# brainwave.net
KiCad netlist of a schematic drawn in EAGLE
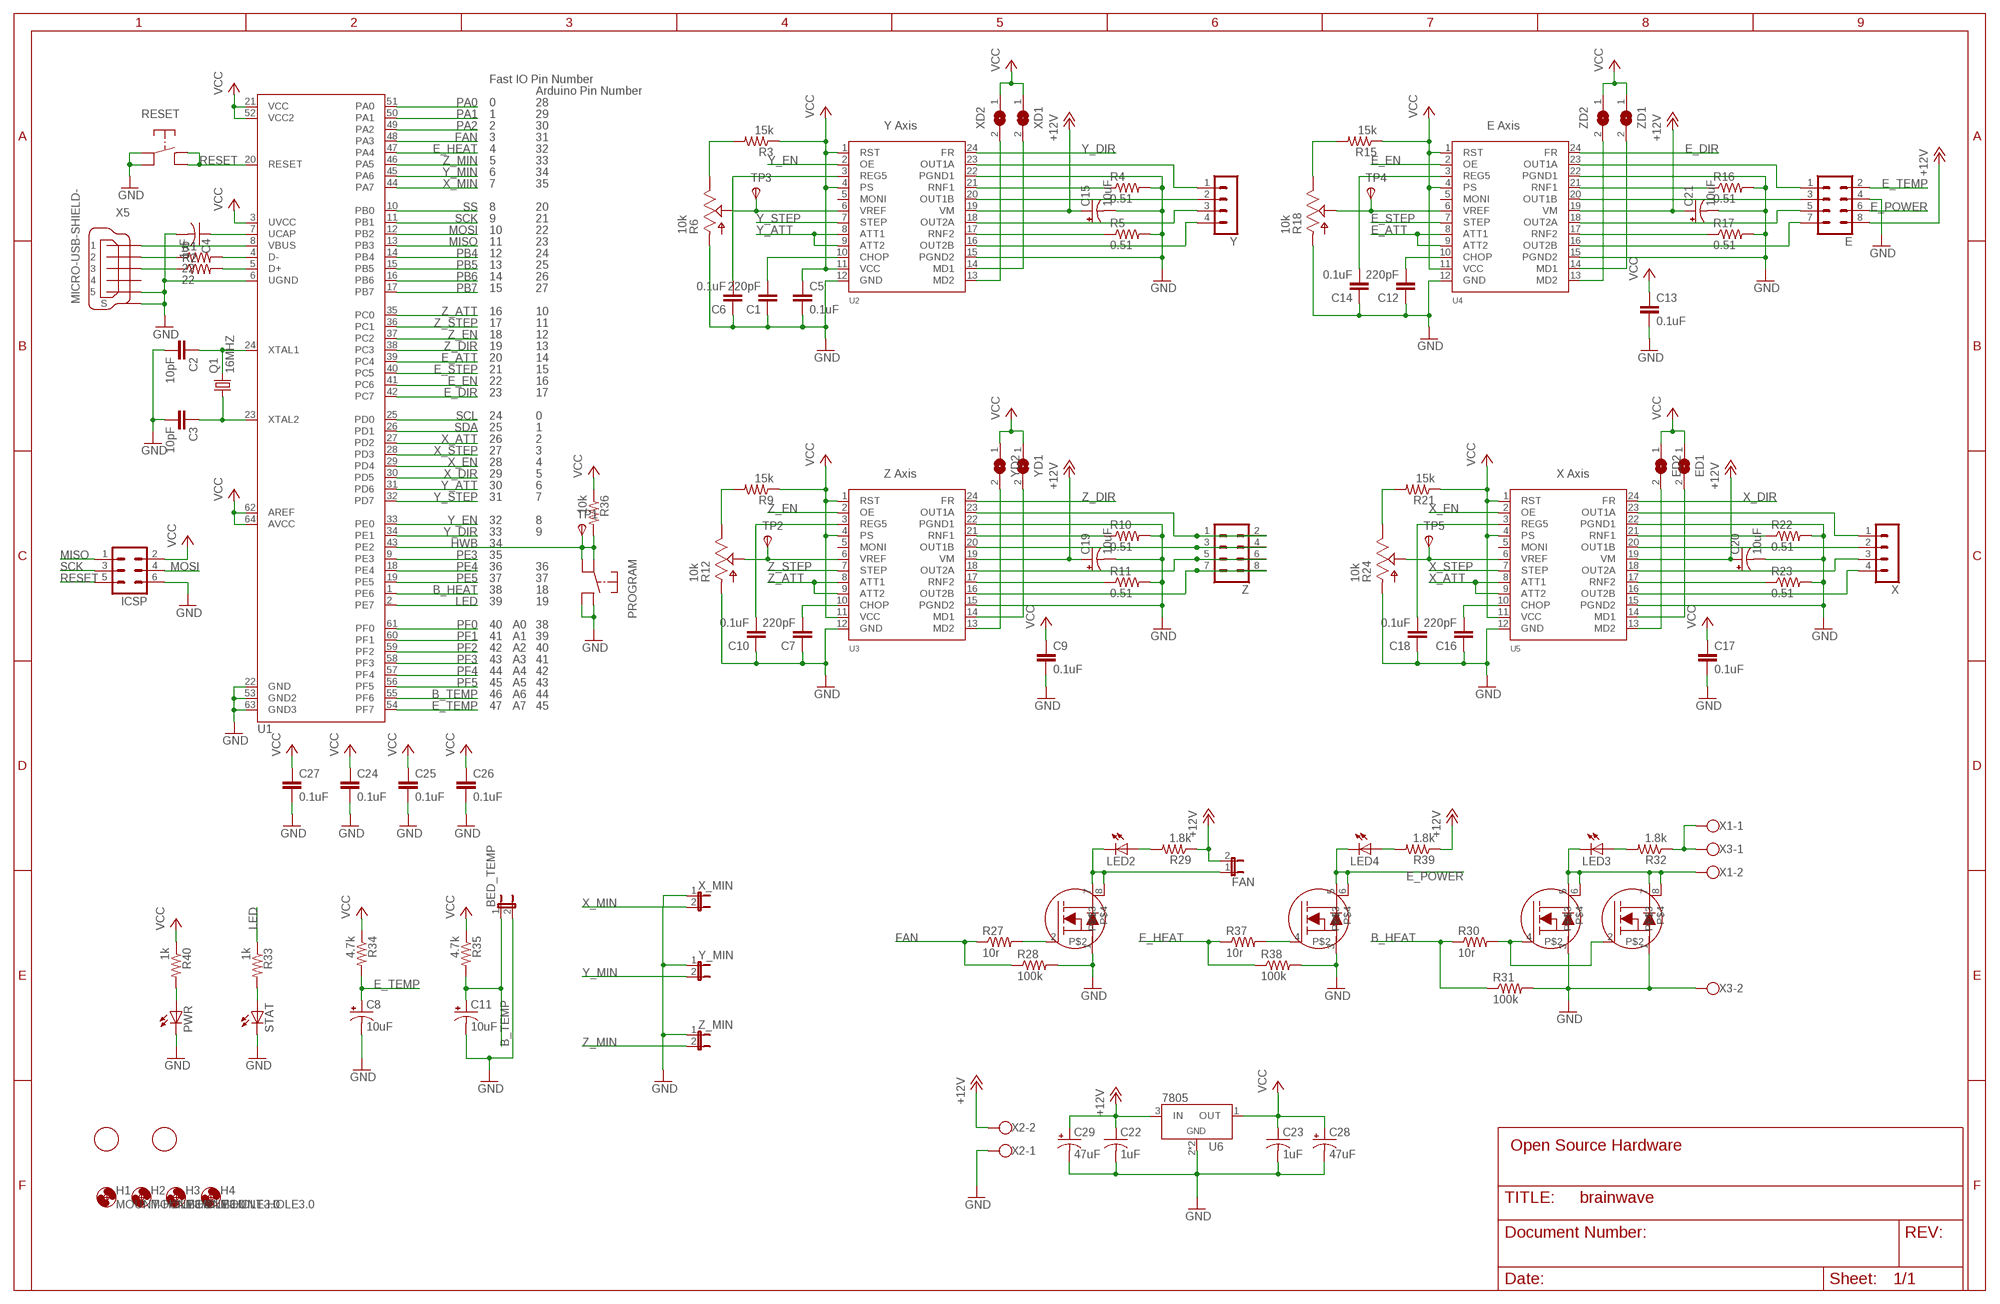
[diagram p0: schematic, sheet 1]

(export (version "E")
  (design (tool "Eeschema 10.0.6"))
  (components
    (comp (ref "BED_TEMP")
      (value "JP1E")
      (footprint "eagle-import:JP1")
      (libsource (lib "eagle-import") (part "JP1E"))
    )
    (comp (ref "C1")
      (value "220pF")
      (footprint "eagle-import:C0603")
      (libsource (lib "eagle-import") (part "C-EUC0603"))
    )
    (comp (ref "C2")
      (value "10pF")
      (footprint "eagle-import:C0603")
      (libsource (lib "eagle-import") (part "C-EUC0603"))
    )
    (comp (ref "C3")
      (value "10pF")
      (footprint "eagle-import:C0603")
      (libsource (lib "eagle-import") (part "C-EUC0603"))
    )
    (comp (ref "C4")
      (value "1uF")
      (footprint "eagle-import:C0603")
      (libsource (lib "eagle-import") (part "C-USC0603"))
    )
    (comp (ref "C5")
      (value "0.1uF")
      (footprint "eagle-import:C0603")
      (libsource (lib "eagle-import") (part "C-EUC0603"))
    )
    (comp (ref "C6")
      (value "0.1uF")
      (footprint "eagle-import:C0603")
      (libsource (lib "eagle-import") (part "C-EUC0603"))
    )
    (comp (ref "C7")
      (value "220pF")
      (footprint "eagle-import:C0603")
      (libsource (lib "eagle-import") (part "C-EUC0603"))
    )
    (comp (ref "C8")
      (value "10uF")
      (footprint "eagle-import:153CLV-0505")
      (libsource (lib "eagle-import") (part "CPOL-US153CLV-0505"))
    )
    (comp (ref "C9")
      (value "0.1uF")
      (footprint "eagle-import:C0603")
      (libsource (lib "eagle-import") (part "C-EUC0603"))
    )
    (comp (ref "C10")
      (value "0.1uF")
      (footprint "eagle-import:C0603")
      (libsource (lib "eagle-import") (part "C-EUC0603"))
    )
    (comp (ref "C11")
      (value "10uF")
      (footprint "eagle-import:153CLV-0505")
      (libsource (lib "eagle-import") (part "CPOL-US153CLV-0505"))
    )
    (comp (ref "C12")
      (value "220pF")
      (footprint "eagle-import:C0603")
      (libsource (lib "eagle-import") (part "C-EUC0603"))
    )
    (comp (ref "C13")
      (value "0.1uF")
      (footprint "eagle-import:C0603")
      (libsource (lib "eagle-import") (part "C-EUC0603"))
    )
    (comp (ref "C14")
      (value "0.1uF")
      (footprint "eagle-import:C0603")
      (libsource (lib "eagle-import") (part "C-EUC0603"))
    )
    (comp (ref "C15")
      (value "10uF")
      (footprint "eagle-import:153CLV-0505")
      (libsource (lib "eagle-import") (part "CPOL-US153CLV-0505"))
    )
    (comp (ref "C16")
      (value "220pF")
      (footprint "eagle-import:C0603")
      (libsource (lib "eagle-import") (part "C-EUC0603"))
    )
    (comp (ref "C17")
      (value "0.1uF")
      (footprint "eagle-import:C0603")
      (libsource (lib "eagle-import") (part "C-EUC0603"))
    )
    (comp (ref "C18")
      (value "0.1uF")
      (footprint "eagle-import:C0603")
      (libsource (lib "eagle-import") (part "C-EUC0603"))
    )
    (comp (ref "C19")
      (value "10uF")
      (footprint "eagle-import:153CLV-0505")
      (libsource (lib "eagle-import") (part "CPOL-US153CLV-0505"))
    )
    (comp (ref "C20")
      (value "10uF")
      (footprint "eagle-import:153CLV-0505")
      (libsource (lib "eagle-import") (part "CPOL-US153CLV-0505"))
    )
    (comp (ref "C21")
      (value "10uF")
      (footprint "eagle-import:153CLV-0505")
      (libsource (lib "eagle-import") (part "CPOL-US153CLV-0505"))
    )
    (comp (ref "C22")
      (value "1uF")
      (footprint "eagle-import:C0603")
      (libsource (lib "eagle-import") (part "C-USC0603"))
    )
    (comp (ref "C23")
      (value "1uF")
      (footprint "eagle-import:C0603")
      (libsource (lib "eagle-import") (part "C-USC0603"))
    )
    (comp (ref "C24")
      (value "0.1uF")
      (footprint "eagle-import:C0603")
      (libsource (lib "eagle-import") (part "C-EUC0603"))
    )
    (comp (ref "C25")
      (value "0.1uF")
      (footprint "eagle-import:C0603")
      (libsource (lib "eagle-import") (part "C-EUC0603"))
    )
    (comp (ref "C26")
      (value "0.1uF")
      (footprint "eagle-import:C0603")
      (libsource (lib "eagle-import") (part "C-EUC0603"))
    )
    (comp (ref "C27")
      (value "0.1uF")
      (footprint "eagle-import:C0603")
      (libsource (lib "eagle-import") (part "C-EUC0603"))
    )
    (comp (ref "C28")
      (value "47uF")
      (footprint "eagle-import:153CLV-0605")
      (libsource (lib "eagle-import") (part "CPOL-US153CLV-0605"))
    )
    (comp (ref "C29")
      (value "47uF")
      (footprint "eagle-import:153CLV-0605")
      (libsource (lib "eagle-import") (part "CPOL-US153CLV-0605"))
    )
    (comp (ref "E")
      (value "MA04-2")
      (footprint "eagle-import:MA04-2")
      (libsource (lib "eagle-import") (part "MA04-2"))
    )
    (comp (ref "ED1") (value "SJ") (footprint "eagle-import:SJ") (libsource (lib "eagle-import") (part "SJ")))
    (comp (ref "ED2") (value "SJ") (footprint "eagle-import:SJ") (libsource (lib "eagle-import") (part "SJ")))
    (comp (ref "FAN")
      (value "JP1E")
      (footprint "eagle-import:JP1")
      (libsource (lib "eagle-import") (part "JP1E"))
    )
    (comp (ref "H1")
      (value "MOUNT-HOLE3.0")
      (footprint "eagle-import:3,0")
      (libsource (lib "eagle-import") (part "MOUNT-HOLE3.0"))
    )
    (comp (ref "H2")
      (value "MOUNT-HOLE3.0")
      (footprint "eagle-import:3,0")
      (libsource (lib "eagle-import") (part "MOUNT-HOLE3.0"))
    )
    (comp (ref "H3")
      (value "MOUNT-HOLE3.0")
      (footprint "eagle-import:3,0")
      (libsource (lib "eagle-import") (part "MOUNT-HOLE3.0"))
    )
    (comp (ref "H4")
      (value "MOUNT-HOLE3.0")
      (footprint "eagle-import:3,0")
      (libsource (lib "eagle-import") (part "MOUNT-HOLE3.0"))
    )
    (comp (ref "ICSP")
      (value "MA03-2")
      (footprint "eagle-import:MA03-2")
      (libsource (lib "eagle-import") (part "MA03-2"))
    )
    (comp (ref "LED2")
      (value "LEDCHIPLED_0805")
      (footprint "eagle-import:CHIPLED_0805")
      (libsource (lib "eagle-import") (part "LEDCHIPLED_0805"))
    )
    (comp (ref "LED3")
      (value "LEDCHIPLED_0805")
      (footprint "eagle-import:CHIPLED_0805")
      (libsource (lib "eagle-import") (part "LEDCHIPLED_0805"))
    )
    (comp (ref "LED4")
      (value "LEDCHIPLED_0805")
      (footprint "eagle-import:CHIPLED_0805")
      (libsource (lib "eagle-import") (part "LEDCHIPLED_0805"))
    )
    (comp (ref "PROGRAM")
      (value "PTS645SMT")
      (footprint "eagle-import:PTS645-SMTR")
      (libsource (lib "eagle-import") (part "PTS645SMT"))
    )
    (comp (ref "PWR")
      (value "LEDCHIPLED_0805")
      (footprint "eagle-import:CHIPLED_0805")
      (libsource (lib "eagle-import") (part "LEDCHIPLED_0805"))
    )
    (comp (ref "Q1")
      (value "16MHZ")
      (footprint "eagle-import:CSM-3X")
      (libsource (lib "eagle-import") (part "CRYSTALCSM-3X"))
    )
    (comp (ref "R1")
      (value "22")
      (footprint "eagle-import:R0603")
      (libsource (lib "eagle-import") (part "R-US_R0603"))
    )
    (comp (ref "R2")
      (value "22")
      (footprint "eagle-import:R0603")
      (libsource (lib "eagle-import") (part "R-US_R0603"))
    )
    (comp (ref "R3")
      (value "15k")
      (footprint "eagle-import:R0603")
      (libsource (lib "eagle-import") (part "R-US_R0603"))
    )
    (comp (ref "R4")
      (value "0.51")
      (footprint "eagle-import:R2512")
      (libsource (lib "eagle-import") (part "R-US_R2512"))
    )
    (comp (ref "R5")
      (value "0.51")
      (footprint "eagle-import:R2512")
      (libsource (lib "eagle-import") (part "R-US_R2512"))
    )
    (comp (ref "R6")
      (value "10k")
      (footprint "eagle-import:PVZ3A")
      (libsource (lib "eagle-import") (part "PVZ3A"))
    )
    (comp (ref "R9")
      (value "15k")
      (footprint "eagle-import:R0603")
      (libsource (lib "eagle-import") (part "R-US_R0603"))
    )
    (comp (ref "R10")
      (value "0.51")
      (footprint "eagle-import:R2512")
      (libsource (lib "eagle-import") (part "R-US_R2512"))
    )
    (comp (ref "R11")
      (value "0.51")
      (footprint "eagle-import:R2512")
      (libsource (lib "eagle-import") (part "R-US_R2512"))
    )
    (comp (ref "R12")
      (value "10k")
      (footprint "eagle-import:PVZ3A")
      (libsource (lib "eagle-import") (part "PVZ3A"))
    )
    (comp (ref "R15")
      (value "15k")
      (footprint "eagle-import:R0603")
      (libsource (lib "eagle-import") (part "R-US_R0603"))
    )
    (comp (ref "R16")
      (value "0.51")
      (footprint "eagle-import:R2512")
      (libsource (lib "eagle-import") (part "R-US_R2512"))
    )
    (comp (ref "R17")
      (value "0.51")
      (footprint "eagle-import:R2512")
      (libsource (lib "eagle-import") (part "R-US_R2512"))
    )
    (comp (ref "R18")
      (value "10k")
      (footprint "eagle-import:PVZ3A")
      (libsource (lib "eagle-import") (part "PVZ3A"))
    )
    (comp (ref "R21")
      (value "15k")
      (footprint "eagle-import:R0603")
      (libsource (lib "eagle-import") (part "R-US_R0603"))
    )
    (comp (ref "R22")
      (value "0.51")
      (footprint "eagle-import:R2512")
      (libsource (lib "eagle-import") (part "R-US_R2512"))
    )
    (comp (ref "R23")
      (value "0.51")
      (footprint "eagle-import:R2512")
      (libsource (lib "eagle-import") (part "R-US_R2512"))
    )
    (comp (ref "R24")
      (value "10k")
      (footprint "eagle-import:PVZ3A")
      (libsource (lib "eagle-import") (part "PVZ3A"))
    )
    (comp (ref "R27")
      (value "10r")
      (footprint "eagle-import:R0603")
      (libsource (lib "eagle-import") (part "R-US_R0603"))
    )
    (comp (ref "R28")
      (value "100k")
      (footprint "eagle-import:R0603")
      (libsource (lib "eagle-import") (part "R-US_R0603"))
    )
    (comp (ref "R29")
      (value "1.8k")
      (footprint "eagle-import:R0603")
      (libsource (lib "eagle-import") (part "R-US_R0603"))
    )
    (comp (ref "R30")
      (value "10r")
      (footprint "eagle-import:R0603")
      (libsource (lib "eagle-import") (part "R-US_R0603"))
    )
    (comp (ref "R31")
      (value "100k")
      (footprint "eagle-import:R0603")
      (libsource (lib "eagle-import") (part "R-US_R0603"))
    )
    (comp (ref "R32")
      (value "1.8k")
      (footprint "eagle-import:R0603")
      (libsource (lib "eagle-import") (part "R-US_R0603"))
    )
    (comp (ref "R33")
      (value "1k")
      (footprint "eagle-import:R0603")
      (libsource (lib "eagle-import") (part "R-US_R0603"))
    )
    (comp (ref "R34")
      (value "4.7k")
      (footprint "eagle-import:R0603")
      (libsource (lib "eagle-import") (part "R-US_R0603"))
    )
    (comp (ref "R35")
      (value "4.7k")
      (footprint "eagle-import:R0603")
      (libsource (lib "eagle-import") (part "R-US_R0603"))
    )
    (comp (ref "R36")
      (value "10k")
      (footprint "eagle-import:R0603")
      (libsource (lib "eagle-import") (part "R-US_R0603"))
    )
    (comp (ref "R37")
      (value "10r")
      (footprint "eagle-import:R0603")
      (libsource (lib "eagle-import") (part "R-US_R0603"))
    )
    (comp (ref "R38")
      (value "100k")
      (footprint "eagle-import:R0603")
      (libsource (lib "eagle-import") (part "R-US_R0603"))
    )
    (comp (ref "R39")
      (value "1.8k")
      (footprint "eagle-import:R0603")
      (libsource (lib "eagle-import") (part "R-US_R0603"))
    )
    (comp (ref "R40")
      (value "1k")
      (footprint "eagle-import:R0603")
      (libsource (lib "eagle-import") (part "R-US_R0603"))
    )
    (comp (ref "RESET")
      (value "PTS645SMT")
      (footprint "eagle-import:PTS645-SMTR")
      (libsource (lib "eagle-import") (part "PTS645SMT"))
    )
    (comp (ref "STAT")
      (value "LEDCHIPLED_0805")
      (footprint "eagle-import:CHIPLED_0805")
      (libsource (lib "eagle-import") (part "LEDCHIPLED_0805"))
    )
    (comp (ref "TP1")
      (value "TPSTP08R")
      (footprint "eagle-import:TP08R")
      (libsource (lib "eagle-import") (part "TPSTP08R"))
    )
    (comp (ref "TP2")
      (value "TPSTP08R")
      (footprint "eagle-import:TP08R")
      (libsource (lib "eagle-import") (part "TPSTP08R"))
    )
    (comp (ref "TP3")
      (value "TPSTP08R")
      (footprint "eagle-import:TP08R")
      (libsource (lib "eagle-import") (part "TPSTP08R"))
    )
    (comp (ref "TP4")
      (value "TPSTP08R")
      (footprint "eagle-import:TP08R")
      (libsource (lib "eagle-import") (part "TPSTP08R"))
    )
    (comp (ref "TP5")
      (value "TPSTP08R")
      (footprint "eagle-import:TP08R")
      (libsource (lib "eagle-import") (part "TPSTP08R"))
    )
    (comp (ref "U$1")
      (value "FIDUCIAL")
      (footprint "eagle-import:FIDUCIAL_1MM")
      (libsource (lib "eagle-import") (part "FIDUCIAL"))
    )
    (comp (ref "U$2")
      (value "FIDUCIAL")
      (footprint "eagle-import:FIDUCIAL_1MM")
      (libsource (lib "eagle-import") (part "FIDUCIAL"))
    )
    (comp (ref "U1")
      (value "AT90USB64/128")
      (footprint "eagle-import:TQFP64")
      (libsource (lib "eagle-import") (part "AT90USB64/128"))
    )
    (comp (ref "U2")
      (value "LV8713T")
      (footprint "eagle-import:TSSOP24")
      (libsource (lib "eagle-import") (part "LV8713T"))
    )
    (comp (ref "U3")
      (value "LV8713T")
      (footprint "eagle-import:TSSOP24")
      (libsource (lib "eagle-import") (part "LV8713T"))
    )
    (comp (ref "U4")
      (value "LV8713T")
      (footprint "eagle-import:TSSOP24")
      (libsource (lib "eagle-import") (part "LV8713T"))
    )
    (comp (ref "U5")
      (value "LV8713T")
      (footprint "eagle-import:TSSOP24")
      (libsource (lib "eagle-import") (part "LV8713T"))
    )
    (comp (ref "U6")
      (value "7805")
      (footprint "eagle-import:SOT89")
      (libsource (lib "eagle-import") (part "78"))
    )
    (comp (ref "U7")
      (value "IRF8313PBF")
      (footprint "eagle-import:SO8")
      (libsource (lib "eagle-import") (part "IRF8313PBF"))
    )
    (comp (ref "U8")
      (value "IRF8313PBF")
      (footprint "eagle-import:SO8")
      (libsource (lib "eagle-import") (part "IRF8313PBF"))
    )
    (comp (ref "X")
      (value "MA04-1")
      (footprint "eagle-import:MA04-1")
      (libsource (lib "eagle-import") (part "MA04-1"))
    )
    (comp (ref "X1")
      (value "W237-102")
      (footprint "eagle-import:W237-102")
      (fields
        (field (name "MPN") "237-102")
        (field (name "MPN_1") "237-102")
        (field (name "OC_FARNELL") "unknown")
        (field (name "OC_NEWARK") "70K9898")
      )
      (libsource (lib "eagle-import") (part "W237-102"))
    )
    (comp (ref "X2")
      (value "W237-102")
      (footprint "eagle-import:W237-102")
      (fields (field (name "MPN") "237-102"))
      (libsource (lib "eagle-import") (part "W237-102"))
    )
    (comp (ref "X3")
      (value "W237-102")
      (footprint "eagle-import:W237-102")
      (fields
        (field (name "MPN") "237-102")
        (field (name "MPN_1") "237-102")
        (field (name "OC_FARNELL") "unknown")
        (field (name "OC_NEWARK") "70K9898")
      )
      (libsource (lib "eagle-import") (part "W237-102"))
    )
    (comp (ref "X5")
      (value "MICRO-USB-SHIELD-")
      (footprint "eagle-import:10118192-0001LF")
      (libsource (lib "eagle-import") (part "MICRO-USB-SHIELD-"))
    )
    (comp (ref "XD1") (value "SJ") (footprint "eagle-import:SJ") (libsource (lib "eagle-import") (part "SJ")))
    (comp (ref "XD2") (value "SJ") (footprint "eagle-import:SJ") (libsource (lib "eagle-import") (part "SJ")))
    (comp (ref "X_MIN")
      (value "JP1E")
      (footprint "eagle-import:JP1")
      (libsource (lib "eagle-import") (part "JP1E"))
    )
    (comp (ref "Y")
      (value "MA04-1")
      (footprint "eagle-import:MA04-1")
      (libsource (lib "eagle-import") (part "MA04-1"))
    )
    (comp (ref "YD1") (value "SJ") (footprint "eagle-import:SJ") (libsource (lib "eagle-import") (part "SJ")))
    (comp (ref "YD2") (value "SJ") (footprint "eagle-import:SJ") (libsource (lib "eagle-import") (part "SJ")))
    (comp (ref "Y_MIN")
      (value "JP1E")
      (footprint "eagle-import:JP1")
      (libsource (lib "eagle-import") (part "JP1E"))
    )
    (comp (ref "Z")
      (value "MA04-2")
      (footprint "eagle-import:MA04-2")
      (libsource (lib "eagle-import") (part "MA04-2"))
    )
    (comp (ref "ZD1") (value "SJ") (footprint "eagle-import:SJ") (libsource (lib "eagle-import") (part "SJ")))
    (comp (ref "ZD2") (value "SJ") (footprint "eagle-import:SJ") (libsource (lib "eagle-import") (part "SJ")))
    (comp (ref "Z_MIN")
      (value "JP1E")
      (footprint "eagle-import:JP1")
      (libsource (lib "eagle-import") (part "JP1E"))
    )
  )
  (nets
    (net (code "1") (name "+12V") (class "Default")
      (node (ref "C15") (pin "+") (pinfunction "+_+") (pintype "passive"))
      (node (ref "C19") (pin "+") (pinfunction "+_+") (pintype "passive"))
      (node (ref "C20") (pin "+") (pinfunction "+_+") (pintype "passive"))
      (node (ref "C21") (pin "+") (pinfunction "+_+") (pintype "passive"))
      (node (ref "C22") (pin "1") (pinfunction "1_1") (pintype "passive"))
      (node (ref "C29") (pin "+") (pinfunction "+_+") (pintype "passive"))
      (node (ref "E") (pin "8") (pinfunction "8_8") (pintype "passive"))
      (node (ref "FAN") (pin "2") (pinfunction "2_2") (pintype "passive"))
      (node (ref "R29") (pin "1") (pinfunction "1_1") (pintype "passive"))
      (node (ref "R39") (pin "1") (pinfunction "1_1") (pintype "passive"))
      (node (ref "U2") (pin "19") (pinfunction "VM_19") (pintype "bidirectional"))
      (node (ref "U3") (pin "19") (pinfunction "VM_19") (pintype "bidirectional"))
      (node (ref "U4") (pin "19") (pinfunction "VM_19") (pintype "bidirectional"))
      (node (ref "U5") (pin "19") (pinfunction "VM_19") (pintype "bidirectional"))
      (node (ref "U6") (pin "3") (pinfunction "IN_3") (pintype "input"))
      (node (ref "X2") (pin "2") (pinfunction "KL_2") (pintype "passive"))
    )
    (net (code "2") (name "/B_HEAT") (class "Default")
      (node (ref "R30") (pin "1") (pinfunction "1_1") (pintype "passive"))
      (node (ref "R31") (pin "1") (pinfunction "1_1") (pintype "passive"))
      (node (ref "U1") (pin "1") (pinfunction "PE6_1") (pintype "bidirectional"))
    )
    (net (code "3") (name "/B_TEMP") (class "Default")
      (node (ref "BED_TEMP") (pin "1") (pinfunction "1_1") (pintype "passive"))
      (node (ref "C11") (pin "+") (pinfunction "+_+") (pintype "passive"))
      (node (ref "R35") (pin "2") (pinfunction "2_2") (pintype "passive"))
      (node (ref "U1") (pin "55") (pinfunction "PF6_55") (pintype "bidirectional"))
    )
    (net (code "4") (name "/E_ATT") (class "Default")
      (node (ref "U1") (pin "39") (pinfunction "PC4_39") (pintype "bidirectional"))
      (node (ref "U4") (pin "8") (pinfunction "ATT1_8") (pintype "bidirectional"))
      (node (ref "U4") (pin "9") (pinfunction "ATT2_9") (pintype "bidirectional"))
    )
    (net (code "5") (name "/E_DIR") (class "Default")
      (node (ref "U1") (pin "42") (pinfunction "PC7_42") (pintype "bidirectional"))
      (node (ref "U4") (pin "24") (pinfunction "FR_24") (pintype "bidirectional"))
    )
    (net (code "6") (name "/E_EN") (class "Default")
      (node (ref "U1") (pin "41") (pinfunction "PC6_41") (pintype "bidirectional"))
      (node (ref "U4") (pin "2") (pinfunction "OE_2") (pintype "bidirectional"))
    )
    (net (code "7") (name "/E_HEAT") (class "Default")
      (node (ref "R37") (pin "1") (pinfunction "1_1") (pintype "passive"))
      (node (ref "R38") (pin "1") (pinfunction "1_1") (pintype "passive"))
      (node (ref "U1") (pin "47") (pinfunction "PA4_47") (pintype "bidirectional"))
    )
    (net (code "8") (name "/E_POWER") (class "Default")
      (node (ref "E") (pin "6") (pinfunction "6_6") (pintype "passive"))
      (node (ref "LED4") (pin "C") (pinfunction "C_C") (pintype "passive"))
      (node (ref "U7") (pin "5") (pinfunction "P$3_5") (pintype "bidirectional"))
      (node (ref "U7") (pin "6") (pinfunction "P$4_6") (pintype "bidirectional"))
    )
    (net (code "9") (name "/E_STEP") (class "Default")
      (node (ref "U1") (pin "40") (pinfunction "PC5_40") (pintype "bidirectional"))
      (node (ref "U4") (pin "7") (pinfunction "STEP_7") (pintype "bidirectional"))
    )
    (net (code "10") (name "/E_TEMP") (class "Default")
      (node (ref "C8") (pin "+") (pinfunction "+_+") (pintype "passive"))
      (node (ref "E") (pin "2") (pinfunction "2_2") (pintype "passive"))
      (node (ref "R34") (pin "2") (pinfunction "2_2") (pintype "passive"))
      (node (ref "U1") (pin "54") (pinfunction "PF7_54") (pintype "bidirectional"))
    )
    (net (code "11") (name "/FAN") (class "Default")
      (node (ref "R27") (pin "1") (pinfunction "1_1") (pintype "passive"))
      (node (ref "R28") (pin "1") (pinfunction "1_1") (pintype "passive"))
      (node (ref "U1") (pin "48") (pinfunction "PA3_48") (pintype "bidirectional"))
    )
    (net (code "12") (name "/HWB") (class "Default")
      (node (ref "PROGRAM") (pin "P$1") (pinfunction "P$1_P$1") (pintype "bidirectional"))
      (node (ref "PROGRAM") (pin "P$2") (pinfunction "P$2_P$2") (pintype "bidirectional"))
      (node (ref "R36") (pin "2") (pinfunction "2_2") (pintype "passive"))
      (node (ref "TP1") (pin "TP") (pinfunction "PP_TP") (pintype "input"))
      (node (ref "U1") (pin "43") (pinfunction "PE2_43") (pintype "bidirectional"))
    )
    (net (code "13") (name "/LED") (class "Default")
      (node (ref "R33") (pin "1") (pinfunction "1_1") (pintype "passive"))
      (node (ref "U1") (pin "2") (pinfunction "PE7_2") (pintype "bidirectional"))
    )
    (net (code "14") (name "/MISO") (class "Default")
      (node (ref "ICSP") (pin "1") (pinfunction "1_1") (pintype "passive"))
      (node (ref "U1") (pin "13") (pinfunction "PB3_13") (pintype "bidirectional"))
    )
    (net (code "15") (name "/MOSI") (class "Default")
      (node (ref "ICSP") (pin "4") (pinfunction "4_4") (pintype "passive"))
      (node (ref "U1") (pin "12") (pinfunction "PB2_12") (pintype "bidirectional"))
    )
    (net (code "16") (name "/PA0") (class "Default")
      (node (ref "U1") (pin "51") (pinfunction "PA0_51") (pintype "bidirectional"))
    )
    (net (code "17") (name "/PA1") (class "Default")
      (node (ref "U1") (pin "50") (pinfunction "PA1_50") (pintype "bidirectional"))
    )
    (net (code "18") (name "/PA2") (class "Default")
      (node (ref "U1") (pin "49") (pinfunction "PA2_49") (pintype "bidirectional"))
    )
    (net (code "19") (name "/PB4") (class "Default")
      (node (ref "U1") (pin "14") (pinfunction "PB4_14") (pintype "bidirectional"))
    )
    (net (code "20") (name "/PB5") (class "Default")
      (node (ref "U1") (pin "15") (pinfunction "PB5_15") (pintype "bidirectional"))
    )
    (net (code "21") (name "/PB6") (class "Default")
      (node (ref "U1") (pin "16") (pinfunction "PB6_16") (pintype "bidirectional"))
    )
    (net (code "22") (name "/PB7") (class "Default")
      (node (ref "U1") (pin "17") (pinfunction "PB7_17") (pintype "bidirectional"))
    )
    (net (code "23") (name "/PE3") (class "Default")
      (node (ref "U1") (pin "9") (pinfunction "PE3_9") (pintype "bidirectional"))
    )
    (net (code "24") (name "/PE4") (class "Default")
      (node (ref "U1") (pin "18") (pinfunction "PE4_18") (pintype "bidirectional"))
    )
    (net (code "25") (name "/PE5") (class "Default")
      (node (ref "U1") (pin "19") (pinfunction "PE5_19") (pintype "bidirectional"))
    )
    (net (code "26") (name "/PF0") (class "Default")
      (node (ref "U1") (pin "61") (pinfunction "PF0_61") (pintype "bidirectional"))
    )
    (net (code "27") (name "/PF1") (class "Default")
      (node (ref "U1") (pin "60") (pinfunction "PF1_60") (pintype "bidirectional"))
    )
    (net (code "28") (name "/PF2") (class "Default")
      (node (ref "U1") (pin "59") (pinfunction "PF2_59") (pintype "bidirectional"))
    )
    (net (code "29") (name "/PF3") (class "Default")
      (node (ref "U1") (pin "58") (pinfunction "PF3_58") (pintype "bidirectional"))
    )
    (net (code "30") (name "/PF4") (class "Default")
      (node (ref "U1") (pin "57") (pinfunction "PF4_57") (pintype "bidirectional"))
    )
    (net (code "31") (name "/PF5") (class "Default")
      (node (ref "U1") (pin "56") (pinfunction "PF5_56") (pintype "bidirectional"))
    )
    (net (code "32") (name "/RESET") (class "Default")
      (node (ref "ICSP") (pin "5") (pinfunction "5_5") (pintype "passive"))
      (node (ref "RESET") (pin "P$3") (pinfunction "P$3_P$3") (pintype "bidirectional"))
      (node (ref "RESET") (pin "P$4") (pinfunction "P$4_P$4") (pintype "bidirectional"))
      (node (ref "U1") (pin "20") (pinfunction "RESET_20") (pintype "bidirectional"))
    )
    (net (code "33") (name "/SCK") (class "Default")
      (node (ref "ICSP") (pin "3") (pinfunction "3_3") (pintype "passive"))
      (node (ref "U1") (pin "11") (pinfunction "PB1_11") (pintype "bidirectional"))
    )
    (net (code "34") (name "/SCL") (class "Default")
      (node (ref "U1") (pin "25") (pinfunction "PD0_25") (pintype "bidirectional"))
    )
    (net (code "35") (name "/SDA") (class "Default")
      (node (ref "U1") (pin "26") (pinfunction "PD1_26") (pintype "bidirectional"))
    )
    (net (code "36") (name "/SS") (class "Default")
      (node (ref "U1") (pin "10") (pinfunction "PB0_10") (pintype "bidirectional"))
    )
    (net (code "37") (name "/X_ATT") (class "Default")
      (node (ref "U1") (pin "27") (pinfunction "PD2_27") (pintype "bidirectional"))
      (node (ref "U5") (pin "8") (pinfunction "ATT1_8") (pintype "bidirectional"))
      (node (ref "U5") (pin "9") (pinfunction "ATT2_9") (pintype "bidirectional"))
    )
    (net (code "38") (name "/X_DIR") (class "Default")
      (node (ref "U1") (pin "30") (pinfunction "PD5_30") (pintype "bidirectional"))
      (node (ref "U5") (pin "24") (pinfunction "FR_24") (pintype "bidirectional"))
    )
    (net (code "39") (name "/X_EN") (class "Default")
      (node (ref "U1") (pin "29") (pinfunction "PD4_29") (pintype "bidirectional"))
      (node (ref "U5") (pin "2") (pinfunction "OE_2") (pintype "bidirectional"))
    )
    (net (code "40") (name "/X_MIN") (class "Default")
      (node (ref "U1") (pin "44") (pinfunction "PA7_44") (pintype "bidirectional"))
      (node (ref "X_MIN") (pin "2") (pinfunction "2_2") (pintype "passive"))
    )
    (net (code "41") (name "/X_STEP") (class "Default")
      (node (ref "U1") (pin "28") (pinfunction "PD3_28") (pintype "bidirectional"))
      (node (ref "U5") (pin "7") (pinfunction "STEP_7") (pintype "bidirectional"))
    )
    (net (code "42") (name "/Y_ATT") (class "Default")
      (node (ref "U1") (pin "31") (pinfunction "PD6_31") (pintype "bidirectional"))
      (node (ref "U2") (pin "8") (pinfunction "ATT1_8") (pintype "bidirectional"))
      (node (ref "U2") (pin "9") (pinfunction "ATT2_9") (pintype "bidirectional"))
    )
    (net (code "43") (name "/Y_DIR") (class "Default")
      (node (ref "U1") (pin "34") (pinfunction "PE1_34") (pintype "bidirectional"))
      (node (ref "U2") (pin "24") (pinfunction "FR_24") (pintype "bidirectional"))
    )
    (net (code "44") (name "/Y_EN") (class "Default")
      (node (ref "U1") (pin "33") (pinfunction "PE0_33") (pintype "bidirectional"))
      (node (ref "U2") (pin "2") (pinfunction "OE_2") (pintype "bidirectional"))
    )
    (net (code "45") (name "/Y_MIN") (class "Default")
      (node (ref "U1") (pin "45") (pinfunction "PA6_45") (pintype "bidirectional"))
      (node (ref "Y_MIN") (pin "2") (pinfunction "2_2") (pintype "passive"))
    )
    (net (code "46") (name "/Y_STEP") (class "Default")
      (node (ref "U1") (pin "32") (pinfunction "PD7_32") (pintype "bidirectional"))
      (node (ref "U2") (pin "7") (pinfunction "STEP_7") (pintype "bidirectional"))
    )
    (net (code "47") (name "/Z_ATT") (class "Default")
      (node (ref "U1") (pin "35") (pinfunction "PC0_35") (pintype "bidirectional"))
      (node (ref "U3") (pin "8") (pinfunction "ATT1_8") (pintype "bidirectional"))
      (node (ref "U3") (pin "9") (pinfunction "ATT2_9") (pintype "bidirectional"))
    )
    (net (code "48") (name "/Z_DIR") (class "Default")
      (node (ref "U1") (pin "38") (pinfunction "PC3_38") (pintype "bidirectional"))
      (node (ref "U3") (pin "24") (pinfunction "FR_24") (pintype "bidirectional"))
    )
    (net (code "49") (name "/Z_EN") (class "Default")
      (node (ref "U1") (pin "37") (pinfunction "PC2_37") (pintype "bidirectional"))
      (node (ref "U3") (pin "2") (pinfunction "OE_2") (pintype "bidirectional"))
    )
    (net (code "50") (name "/Z_MIN") (class "Default")
      (node (ref "U1") (pin "46") (pinfunction "PA5_46") (pintype "bidirectional"))
      (node (ref "Z_MIN") (pin "2") (pinfunction "2_2") (pintype "passive"))
    )
    (net (code "51") (name "/Z_STEP") (class "Default")
      (node (ref "U1") (pin "36") (pinfunction "PC1_36") (pintype "bidirectional"))
      (node (ref "U3") (pin "7") (pinfunction "STEP_7") (pintype "bidirectional"))
    )
    (net (code "52") (name "GND") (class "Default")
      (node (ref "BED_TEMP") (pin "2") (pinfunction "2_2") (pintype "passive"))
      (node (ref "C1") (pin "1") (pinfunction "1_1") (pintype "passive"))
      (node (ref "C10") (pin "1") (pinfunction "1_1") (pintype "passive"))
      (node (ref "C11") (pin "-") (pinfunction "-_-") (pintype "passive"))
      (node (ref "C12") (pin "1") (pinfunction "1_1") (pintype "passive"))
      (node (ref "C13") (pin "2") (pinfunction "2_2") (pintype "passive"))
      (node (ref "C14") (pin "1") (pinfunction "1_1") (pintype "passive"))
      (node (ref "C15") (pin "-") (pinfunction "-_-") (pintype "passive"))
      (node (ref "C16") (pin "1") (pinfunction "1_1") (pintype "passive"))
      (node (ref "C17") (pin "2") (pinfunction "2_2") (pintype "passive"))
      (node (ref "C18") (pin "1") (pinfunction "1_1") (pintype "passive"))
      (node (ref "C19") (pin "-") (pinfunction "-_-") (pintype "passive"))
      (node (ref "C2") (pin "2") (pinfunction "2_2") (pintype "passive"))
      (node (ref "C20") (pin "-") (pinfunction "-_-") (pintype "passive"))
      (node (ref "C21") (pin "-") (pinfunction "-_-") (pintype "passive"))
      (node (ref "C22") (pin "2") (pinfunction "2_2") (pintype "passive"))
      (node (ref "C23") (pin "2") (pinfunction "2_2") (pintype "passive"))
      (node (ref "C24") (pin "2") (pinfunction "2_2") (pintype "passive"))
      (node (ref "C25") (pin "2") (pinfunction "2_2") (pintype "passive"))
      (node (ref "C26") (pin "2") (pinfunction "2_2") (pintype "passive"))
      (node (ref "C27") (pin "2") (pinfunction "2_2") (pintype "passive"))
      (node (ref "C28") (pin "-") (pinfunction "-_-") (pintype "passive"))
      (node (ref "C29") (pin "-") (pinfunction "-_-") (pintype "passive"))
      (node (ref "C3") (pin "2") (pinfunction "2_2") (pintype "passive"))
      (node (ref "C4") (pin "2") (pinfunction "2_2") (pintype "passive"))
      (node (ref "C5") (pin "2") (pinfunction "2_2") (pintype "passive"))
      (node (ref "C6") (pin "1") (pinfunction "1_1") (pintype "passive"))
      (node (ref "C7") (pin "1") (pinfunction "1_1") (pintype "passive"))
      (node (ref "C8") (pin "-") (pinfunction "-_-") (pintype "passive"))
      (node (ref "C9") (pin "2") (pinfunction "2_2") (pintype "passive"))
      (node (ref "E") (pin "4") (pinfunction "4_4") (pintype "passive"))
      (node (ref "ICSP") (pin "6") (pinfunction "6_6") (pintype "passive"))
      (node (ref "PROGRAM") (pin "P$3") (pinfunction "P$3_P$3") (pintype "bidirectional"))
      (node (ref "PROGRAM") (pin "P$4") (pinfunction "P$4_P$4") (pintype "bidirectional"))
      (node (ref "PWR") (pin "C") (pinfunction "C_C") (pintype "passive"))
      (node (ref "R10") (pin "2") (pinfunction "2_2") (pintype "passive"))
      (node (ref "R11") (pin "2") (pinfunction "2_2") (pintype "passive"))
      (node (ref "R12") (pin "P$1") (pinfunction "P$1_P$1") (pintype "bidirectional"))
      (node (ref "R16") (pin "2") (pinfunction "2_2") (pintype "passive"))
      (node (ref "R17") (pin "2") (pinfunction "2_2") (pintype "passive"))
      (node (ref "R18") (pin "P$1") (pinfunction "P$1_P$1") (pintype "bidirectional"))
      (node (ref "R22") (pin "2") (pinfunction "2_2") (pintype "passive"))
      (node (ref "R23") (pin "2") (pinfunction "2_2") (pintype "passive"))
      (node (ref "R24") (pin "P$1") (pinfunction "P$1_P$1") (pintype "bidirectional"))
      (node (ref "R28") (pin "2") (pinfunction "2_2") (pintype "passive"))
      (node (ref "R31") (pin "2") (pinfunction "2_2") (pintype "passive"))
      (node (ref "R38") (pin "2") (pinfunction "2_2") (pintype "passive"))
      (node (ref "R4") (pin "2") (pinfunction "2_2") (pintype "passive"))
      (node (ref "R5") (pin "2") (pinfunction "2_2") (pintype "passive"))
      (node (ref "R6") (pin "P$1") (pinfunction "P$1_P$1") (pintype "bidirectional"))
      (node (ref "RESET") (pin "P$1") (pinfunction "P$1_P$1") (pintype "bidirectional"))
      (node (ref "RESET") (pin "P$2") (pinfunction "P$2_P$2") (pintype "bidirectional"))
      (node (ref "STAT") (pin "C") (pinfunction "C_C") (pintype "passive"))
      (node (ref "U1") (pin "22") (pinfunction "GND_22") (pintype "bidirectional"))
      (node (ref "U1") (pin "53") (pinfunction "GND2_53") (pintype "bidirectional"))
      (node (ref "U1") (pin "6") (pinfunction "UGND_6") (pintype "bidirectional"))
      (node (ref "U1") (pin "63") (pinfunction "GND3_63") (pintype "bidirectional"))
      (node (ref "U2") (pin "12") (pinfunction "GND_12") (pintype "bidirectional"))
      (node (ref "U2") (pin "15") (pinfunction "PGND2_15") (pintype "bidirectional"))
      (node (ref "U2") (pin "22") (pinfunction "PGND1_22") (pintype "bidirectional"))
      (node (ref "U3") (pin "12") (pinfunction "GND_12") (pintype "bidirectional"))
      (node (ref "U3") (pin "15") (pinfunction "PGND2_15") (pintype "bidirectional"))
      (node (ref "U3") (pin "22") (pinfunction "PGND1_22") (pintype "bidirectional"))
      (node (ref "U4") (pin "12") (pinfunction "GND_12") (pintype "bidirectional"))
      (node (ref "U4") (pin "15") (pinfunction "PGND2_15") (pintype "bidirectional"))
      (node (ref "U4") (pin "22") (pinfunction "PGND1_22") (pintype "bidirectional"))
      (node (ref "U5") (pin "12") (pinfunction "GND_12") (pintype "bidirectional"))
      (node (ref "U5") (pin "15") (pinfunction "PGND2_15") (pintype "bidirectional"))
      (node (ref "U5") (pin "22") (pinfunction "PGND1_22") (pintype "bidirectional"))
      (node (ref "U6") (pin "2") (pinfunction "GND_2") (pintype "passive"))
      (node (ref "U6") (pin "2@1") (pinfunction "GND_2@1") (pintype "passive"))
      (node (ref "U7") (pin "1") (pinfunction "P$1_1") (pintype "bidirectional"))
      (node (ref "U7") (pin "3") (pinfunction "P$1_3") (pintype "bidirectional"))
      (node (ref "U8") (pin "1") (pinfunction "P$1_1") (pintype "bidirectional"))
      (node (ref "U8") (pin "3") (pinfunction "P$1_3") (pintype "bidirectional"))
      (node (ref "X2") (pin "1") (pinfunction "KL_1") (pintype "passive"))
      (node (ref "X3") (pin "2") (pinfunction "KL_2") (pintype "passive"))
      (node (ref "X5") (pin "5") (pinfunction "5_5") (pintype "input"))
      (node (ref "X5") (pin "M1") (pinfunction "S_M1") (pintype "bidirectional"))
      (node (ref "X5") (pin "M2") (pinfunction "S_M2") (pintype "bidirectional"))
      (node (ref "X5") (pin "M3") (pinfunction "S_M3") (pintype "bidirectional"))
      (node (ref "X5") (pin "M4") (pinfunction "S_M4") (pintype "bidirectional"))
      (node (ref "X5") (pin "M5") (pinfunction "S_M5") (pintype "bidirectional"))
      (node (ref "X5") (pin "M6") (pinfunction "S_M6") (pintype "bidirectional"))
      (node (ref "X_MIN") (pin "1") (pinfunction "1_1") (pintype "passive"))
      (node (ref "Y_MIN") (pin "1") (pinfunction "1_1") (pintype "passive"))
      (node (ref "Z_MIN") (pin "1") (pinfunction "1_1") (pintype "passive"))
    )
    (net (code "53") (name "Net-(LED2-PadA)") (class "Default")
      (node (ref "LED2") (pin "A") (pinfunction "A_A") (pintype "passive"))
      (node (ref "R29") (pin "2") (pinfunction "2_2") (pintype "passive"))
    )
    (net (code "54") (name "Net-(LED3-PadA)") (class "Default")
      (node (ref "LED3") (pin "A") (pinfunction "A_A") (pintype "passive"))
      (node (ref "R32") (pin "2") (pinfunction "2_2") (pintype "passive"))
    )
    (net (code "55") (name "Net-(LED4-PadA)") (class "Default")
      (node (ref "LED4") (pin "A") (pinfunction "A_A") (pintype "passive"))
      (node (ref "R39") (pin "2") (pinfunction "2_2") (pintype "passive"))
    )
    (net (code "56") (name "Net-(PWR-PadA)") (class "Default")
      (node (ref "PWR") (pin "A") (pinfunction "A_A") (pintype "passive"))
      (node (ref "R40") (pin "2") (pinfunction "2_2") (pintype "passive"))
    )
    (net (code "57") (name "Net-(R1-Pad1)") (class "Default")
      (node (ref "R1") (pin "1") (pinfunction "1_1") (pintype "passive"))
      (node (ref "X5") (pin "2") (pinfunction "2_2") (pintype "input"))
    )
    (net (code "58") (name "Net-(R2-Pad1)") (class "Default")
      (node (ref "R2") (pin "1") (pinfunction "1_1") (pintype "passive"))
      (node (ref "X5") (pin "3") (pinfunction "3_3") (pintype "input"))
    )
    (net (code "59") (name "Net-(R3-Pad2)") (class "Default")
      (node (ref "R3") (pin "2") (pinfunction "2_2") (pintype "passive"))
      (node (ref "R6") (pin "P$3") (pinfunction "P$3_P$3") (pintype "bidirectional"))
    )
    (net (code "60") (name "Net-(R12-PadP$3)") (class "Default")
      (node (ref "R12") (pin "P$3") (pinfunction "P$3_P$3") (pintype "bidirectional"))
      (node (ref "R9") (pin "2") (pinfunction "2_2") (pintype "passive"))
    )
    (net (code "61") (name "Net-(R15-Pad2)") (class "Default")
      (node (ref "R15") (pin "2") (pinfunction "2_2") (pintype "passive"))
      (node (ref "R18") (pin "P$3") (pinfunction "P$3_P$3") (pintype "bidirectional"))
    )
    (net (code "62") (name "Net-(R21-Pad2)") (class "Default")
      (node (ref "R21") (pin "2") (pinfunction "2_2") (pintype "passive"))
      (node (ref "R24") (pin "P$3") (pinfunction "P$3_P$3") (pintype "bidirectional"))
    )
    (net (code "63") (name "Net-(R33-Pad2)") (class "Default")
      (node (ref "R33") (pin "2") (pinfunction "2_2") (pintype "passive"))
      (node (ref "STAT") (pin "A") (pinfunction "A_A") (pintype "passive"))
    )
    (net (code "64") (name "Net-(TP2-PP)") (class "Default")
      (node (ref "R12") (pin "P$2") (pinfunction "P$2_P$2") (pintype "bidirectional"))
      (node (ref "TP2") (pin "TP") (pinfunction "PP_TP") (pintype "input"))
      (node (ref "U3") (pin "6") (pinfunction "VREF_6") (pintype "bidirectional"))
    )
    (net (code "65") (name "Net-(TP3-PP)") (class "Default")
      (node (ref "R6") (pin "P$2") (pinfunction "P$2_P$2") (pintype "bidirectional"))
      (node (ref "TP3") (pin "TP") (pinfunction "PP_TP") (pintype "input"))
      (node (ref "U2") (pin "6") (pinfunction "VREF_6") (pintype "bidirectional"))
    )
    (net (code "66") (name "Net-(TP4-PP)") (class "Default")
      (node (ref "R18") (pin "P$2") (pinfunction "P$2_P$2") (pintype "bidirectional"))
      (node (ref "TP4") (pin "TP") (pinfunction "PP_TP") (pintype "input"))
      (node (ref "U4") (pin "6") (pinfunction "VREF_6") (pintype "bidirectional"))
    )
    (net (code "67") (name "Net-(TP5-PP)") (class "Default")
      (node (ref "R24") (pin "P$2") (pinfunction "P$2_P$2") (pintype "bidirectional"))
      (node (ref "TP5") (pin "TP") (pinfunction "PP_TP") (pintype "input"))
      (node (ref "U5") (pin "6") (pinfunction "VREF_6") (pintype "bidirectional"))
    )
    (net (code "68") (name "Net-(U1-D+)") (class "Default")
      (node (ref "R2") (pin "2") (pinfunction "2_2") (pintype "passive"))
      (node (ref "U1") (pin "5") (pinfunction "D+_5") (pintype "bidirectional"))
    )
    (net (code "69") (name "Net-(U1-D-)") (class "Default")
      (node (ref "R1") (pin "2") (pinfunction "2_2") (pintype "passive"))
      (node (ref "U1") (pin "4") (pinfunction "D-_4") (pintype "bidirectional"))
    )
    (net (code "70") (name "Net-(U1-UCAP)") (class "Default")
      (node (ref "C4") (pin "1") (pinfunction "1_1") (pintype "passive"))
      (node (ref "U1") (pin "7") (pinfunction "UCAP_7") (pintype "bidirectional"))
    )
    (net (code "71") (name "Net-(U1-VBUS)") (class "Default")
      (node (ref "U1") (pin "8") (pinfunction "VBUS_8") (pintype "bidirectional"))
      (node (ref "X5") (pin "1") (pinfunction "1_1") (pintype "input"))
    )
    (net (code "72") (name "Net-(U1-XTAL1)") (class "Default")
      (node (ref "C2") (pin "1") (pinfunction "1_1") (pintype "passive"))
      (node (ref "Q1") (pin "2") (pinfunction "2_2") (pintype "passive"))
      (node (ref "U1") (pin "24") (pinfunction "XTAL1_24") (pintype "bidirectional"))
    )
    (net (code "73") (name "Net-(U1-XTAL2)") (class "Default")
      (node (ref "C3") (pin "1") (pinfunction "1_1") (pintype "passive"))
      (node (ref "Q1") (pin "1") (pinfunction "1_1") (pintype "passive"))
      (node (ref "U1") (pin "23") (pinfunction "XTAL2_23") (pintype "bidirectional"))
    )
    (net (code "74") (name "Net-(U2-CHOP)") (class "Default")
      (node (ref "C1") (pin "2") (pinfunction "2_2") (pintype "passive"))
      (node (ref "U2") (pin "10") (pinfunction "CHOP_10") (pintype "bidirectional"))
    )
    (net (code "75") (name "Net-(U2-MD1)") (class "Default")
      (node (ref "U2") (pin "14") (pinfunction "MD1_14") (pintype "bidirectional"))
      (node (ref "XD1") (pin "2") (pinfunction "2_2") (pintype "passive"))
    )
    (net (code "76") (name "Net-(U2-MD2)") (class "Default")
      (node (ref "U2") (pin "13") (pinfunction "MD2_13") (pintype "bidirectional"))
      (node (ref "XD2") (pin "2") (pinfunction "2_2") (pintype "passive"))
    )
    (net (code "77") (name "Net-(U2-OUT1A)") (class "Default")
      (node (ref "U2") (pin "23") (pinfunction "OUT1A_23") (pintype "bidirectional"))
      (node (ref "Y") (pin "1") (pinfunction "1_1") (pintype "passive"))
    )
    (net (code "78") (name "Net-(U2-OUT1B)") (class "Default")
      (node (ref "U2") (pin "20") (pinfunction "OUT1B_20") (pintype "bidirectional"))
      (node (ref "Y") (pin "2") (pinfunction "2_2") (pintype "passive"))
    )
    (net (code "79") (name "Net-(U2-OUT2A)") (class "Default")
      (node (ref "U2") (pin "18") (pinfunction "OUT2A_18") (pintype "bidirectional"))
      (node (ref "Y") (pin "3") (pinfunction "3_3") (pintype "passive"))
    )
    (net (code "80") (name "Net-(U2-OUT2B)") (class "Default")
      (node (ref "U2") (pin "16") (pinfunction "OUT2B_16") (pintype "bidirectional"))
      (node (ref "Y") (pin "4") (pinfunction "4_4") (pintype "passive"))
    )
    (net (code "81") (name "Net-(U2-REG5)") (class "Default")
      (node (ref "C6") (pin "2") (pinfunction "2_2") (pintype "passive"))
      (node (ref "U2") (pin "3") (pinfunction "REG5_3") (pintype "bidirectional"))
    )
    (net (code "82") (name "Net-(U2-RNF1)") (class "Default")
      (node (ref "R4") (pin "1") (pinfunction "1_1") (pintype "passive"))
      (node (ref "U2") (pin "21") (pinfunction "RNF1_21") (pintype "bidirectional"))
    )
    (net (code "83") (name "Net-(U2-RNF2)") (class "Default")
      (node (ref "R5") (pin "1") (pinfunction "1_1") (pintype "passive"))
      (node (ref "U2") (pin "17") (pinfunction "RNF2_17") (pintype "bidirectional"))
    )
    (net (code "84") (name "Net-(U3-CHOP)") (class "Default")
      (node (ref "C7") (pin "2") (pinfunction "2_2") (pintype "passive"))
      (node (ref "U3") (pin "10") (pinfunction "CHOP_10") (pintype "bidirectional"))
    )
    (net (code "85") (name "Net-(U3-MD1)") (class "Default")
      (node (ref "U3") (pin "14") (pinfunction "MD1_14") (pintype "bidirectional"))
      (node (ref "YD1") (pin "2") (pinfunction "2_2") (pintype "passive"))
    )
    (net (code "86") (name "Net-(U3-MD2)") (class "Default")
      (node (ref "U3") (pin "13") (pinfunction "MD2_13") (pintype "bidirectional"))
      (node (ref "YD2") (pin "2") (pinfunction "2_2") (pintype "passive"))
    )
    (net (code "87") (name "Net-(U3-OUT1A)") (class "Default")
      (node (ref "U3") (pin "23") (pinfunction "OUT1A_23") (pintype "bidirectional"))
      (node (ref "Z") (pin "1") (pinfunction "1_1") (pintype "passive"))
      (node (ref "Z") (pin "2") (pinfunction "2_2") (pintype "passive"))
    )
    (net (code "88") (name "Net-(U3-OUT1B)") (class "Default")
      (node (ref "U3") (pin "20") (pinfunction "OUT1B_20") (pintype "bidirectional"))
      (node (ref "Z") (pin "3") (pinfunction "3_3") (pintype "passive"))
      (node (ref "Z") (pin "4") (pinfunction "4_4") (pintype "passive"))
    )
    (net (code "89") (name "Net-(U3-OUT2A)") (class "Default")
      (node (ref "U3") (pin "18") (pinfunction "OUT2A_18") (pintype "bidirectional"))
      (node (ref "Z") (pin "5") (pinfunction "5_5") (pintype "passive"))
      (node (ref "Z") (pin "6") (pinfunction "6_6") (pintype "passive"))
    )
    (net (code "90") (name "Net-(U3-OUT2B)") (class "Default")
      (node (ref "U3") (pin "16") (pinfunction "OUT2B_16") (pintype "bidirectional"))
      (node (ref "Z") (pin "7") (pinfunction "7_7") (pintype "passive"))
      (node (ref "Z") (pin "8") (pinfunction "8_8") (pintype "passive"))
    )
    (net (code "91") (name "Net-(U3-REG5)") (class "Default")
      (node (ref "C10") (pin "2") (pinfunction "2_2") (pintype "passive"))
      (node (ref "U3") (pin "3") (pinfunction "REG5_3") (pintype "bidirectional"))
    )
    (net (code "92") (name "Net-(U3-RNF1)") (class "Default")
      (node (ref "R10") (pin "1") (pinfunction "1_1") (pintype "passive"))
      (node (ref "U3") (pin "21") (pinfunction "RNF1_21") (pintype "bidirectional"))
    )
    (net (code "93") (name "Net-(U3-RNF2)") (class "Default")
      (node (ref "R11") (pin "1") (pinfunction "1_1") (pintype "passive"))
      (node (ref "U3") (pin "17") (pinfunction "RNF2_17") (pintype "bidirectional"))
    )
    (net (code "94") (name "Net-(U4-CHOP)") (class "Default")
      (node (ref "C12") (pin "2") (pinfunction "2_2") (pintype "passive"))
      (node (ref "U4") (pin "10") (pinfunction "CHOP_10") (pintype "bidirectional"))
    )
    (net (code "95") (name "Net-(U4-MD1)") (class "Default")
      (node (ref "U4") (pin "14") (pinfunction "MD1_14") (pintype "bidirectional"))
      (node (ref "ZD1") (pin "2") (pinfunction "2_2") (pintype "passive"))
    )
    (net (code "96") (name "Net-(U4-MD2)") (class "Default")
      (node (ref "U4") (pin "13") (pinfunction "MD2_13") (pintype "bidirectional"))
      (node (ref "ZD2") (pin "2") (pinfunction "2_2") (pintype "passive"))
    )
    (net (code "97") (name "Net-(U4-OUT1A)") (class "Default")
      (node (ref "E") (pin "1") (pinfunction "1_1") (pintype "passive"))
      (node (ref "U4") (pin "23") (pinfunction "OUT1A_23") (pintype "bidirectional"))
    )
    (net (code "98") (name "Net-(U4-OUT1B)") (class "Default")
      (node (ref "E") (pin "3") (pinfunction "3_3") (pintype "passive"))
      (node (ref "U4") (pin "20") (pinfunction "OUT1B_20") (pintype "bidirectional"))
    )
    (net (code "99") (name "Net-(U4-OUT2A)") (class "Default")
      (node (ref "E") (pin "5") (pinfunction "5_5") (pintype "passive"))
      (node (ref "U4") (pin "18") (pinfunction "OUT2A_18") (pintype "bidirectional"))
    )
    (net (code "100") (name "Net-(U4-OUT2B)") (class "Default")
      (node (ref "E") (pin "7") (pinfunction "7_7") (pintype "passive"))
      (node (ref "U4") (pin "16") (pinfunction "OUT2B_16") (pintype "bidirectional"))
    )
    (net (code "101") (name "Net-(U4-REG5)") (class "Default")
      (node (ref "C14") (pin "2") (pinfunction "2_2") (pintype "passive"))
      (node (ref "U4") (pin "3") (pinfunction "REG5_3") (pintype "bidirectional"))
    )
    (net (code "102") (name "Net-(U4-RNF1)") (class "Default")
      (node (ref "R16") (pin "1") (pinfunction "1_1") (pintype "passive"))
      (node (ref "U4") (pin "21") (pinfunction "RNF1_21") (pintype "bidirectional"))
    )
    (net (code "103") (name "Net-(U4-RNF2)") (class "Default")
      (node (ref "R17") (pin "1") (pinfunction "1_1") (pintype "passive"))
      (node (ref "U4") (pin "17") (pinfunction "RNF2_17") (pintype "bidirectional"))
    )
    (net (code "104") (name "Net-(U5-CHOP)") (class "Default")
      (node (ref "C16") (pin "2") (pinfunction "2_2") (pintype "passive"))
      (node (ref "U5") (pin "10") (pinfunction "CHOP_10") (pintype "bidirectional"))
    )
    (net (code "105") (name "Net-(U5-MD1)") (class "Default")
      (node (ref "ED1") (pin "2") (pinfunction "2_2") (pintype "passive"))
      (node (ref "U5") (pin "14") (pinfunction "MD1_14") (pintype "bidirectional"))
    )
    (net (code "106") (name "Net-(U5-MD2)") (class "Default")
      (node (ref "ED2") (pin "2") (pinfunction "2_2") (pintype "passive"))
      (node (ref "U5") (pin "13") (pinfunction "MD2_13") (pintype "bidirectional"))
    )
    (net (code "107") (name "Net-(U5-OUT1A)") (class "Default")
      (node (ref "U5") (pin "23") (pinfunction "OUT1A_23") (pintype "bidirectional"))
      (node (ref "X") (pin "1") (pinfunction "1_1") (pintype "passive"))
    )
    (net (code "108") (name "Net-(U5-OUT1B)") (class "Default")
      (node (ref "U5") (pin "20") (pinfunction "OUT1B_20") (pintype "bidirectional"))
      (node (ref "X") (pin "2") (pinfunction "2_2") (pintype "passive"))
    )
    (net (code "109") (name "Net-(U5-OUT2A)") (class "Default")
      (node (ref "U5") (pin "18") (pinfunction "OUT2A_18") (pintype "bidirectional"))
      (node (ref "X") (pin "3") (pinfunction "3_3") (pintype "passive"))
    )
    (net (code "110") (name "Net-(U5-OUT2B)") (class "Default")
      (node (ref "U5") (pin "16") (pinfunction "OUT2B_16") (pintype "bidirectional"))
      (node (ref "X") (pin "4") (pinfunction "4_4") (pintype "passive"))
    )
    (net (code "111") (name "Net-(U5-REG5)") (class "Default")
      (node (ref "C18") (pin "2") (pinfunction "2_2") (pintype "passive"))
      (node (ref "U5") (pin "3") (pinfunction "REG5_3") (pintype "bidirectional"))
    )
    (net (code "112") (name "Net-(U5-RNF1)") (class "Default")
      (node (ref "R22") (pin "1") (pinfunction "1_1") (pintype "passive"))
      (node (ref "U5") (pin "21") (pinfunction "RNF1_21") (pintype "bidirectional"))
    )
    (net (code "113") (name "Net-(U5-RNF2)") (class "Default")
      (node (ref "R23") (pin "1") (pinfunction "1_1") (pintype "passive"))
      (node (ref "U5") (pin "17") (pinfunction "RNF2_17") (pintype "bidirectional"))
    )
    (net (code "114") (name "Net-(U7A-P$2)") (class "Default")
      (node (ref "R37") (pin "2") (pinfunction "2_2") (pintype "passive"))
      (node (ref "U7") (pin "4") (pinfunction "P$2_4") (pintype "bidirectional"))
    )
    (net (code "115") (name "Net-(U7B-P$2)") (class "Default")
      (node (ref "R27") (pin "2") (pinfunction "2_2") (pintype "passive"))
      (node (ref "U7") (pin "2") (pinfunction "P$2_2") (pintype "bidirectional"))
    )
    (net (code "116") (name "Net-(U7B-P$3)") (class "Default")
      (node (ref "FAN") (pin "1") (pinfunction "1_1") (pintype "passive"))
      (node (ref "LED2") (pin "C") (pinfunction "C_C") (pintype "passive"))
      (node (ref "U7") (pin "7") (pinfunction "P$3_7") (pintype "bidirectional"))
      (node (ref "U7") (pin "8") (pinfunction "P$4_8") (pintype "bidirectional"))
    )
    (net (code "117") (name "Net-(U8A-P$2)") (class "Default")
      (node (ref "R30") (pin "2") (pinfunction "2_2") (pintype "passive"))
      (node (ref "U8") (pin "2") (pinfunction "P$2_2") (pintype "bidirectional"))
      (node (ref "U8") (pin "4") (pinfunction "P$2_4") (pintype "bidirectional"))
    )
    (net (code "118") (name "Net-(U8A-P$3)") (class "Default")
      (node (ref "LED3") (pin "C") (pinfunction "C_C") (pintype "passive"))
      (node (ref "U8") (pin "5") (pinfunction "P$3_5") (pintype "bidirectional"))
      (node (ref "U8") (pin "6") (pinfunction "P$4_6") (pintype "bidirectional"))
      (node (ref "U8") (pin "7") (pinfunction "P$3_7") (pintype "bidirectional"))
      (node (ref "U8") (pin "8") (pinfunction "P$4_8") (pintype "bidirectional"))
      (node (ref "X1") (pin "2") (pinfunction "KL_2") (pintype "passive"))
    )
    (net (code "119") (name "Net-(X1A-KL)") (class "Default")
      (node (ref "R32") (pin "1") (pinfunction "1_1") (pintype "passive"))
      (node (ref "X1") (pin "1") (pinfunction "KL_1") (pintype "passive"))
      (node (ref "X3") (pin "1") (pinfunction "KL_1") (pintype "passive"))
    )
    (net (code "120") (name "VCC") (class "Default")
      (node (ref "C13") (pin "1") (pinfunction "1_1") (pintype "passive"))
      (node (ref "C17") (pin "1") (pinfunction "1_1") (pintype "passive"))
      (node (ref "C23") (pin "1") (pinfunction "1_1") (pintype "passive"))
      (node (ref "C24") (pin "1") (pinfunction "1_1") (pintype "passive"))
      (node (ref "C25") (pin "1") (pinfunction "1_1") (pintype "passive"))
      (node (ref "C26") (pin "1") (pinfunction "1_1") (pintype "passive"))
      (node (ref "C27") (pin "1") (pinfunction "1_1") (pintype "passive"))
      (node (ref "C28") (pin "+") (pinfunction "+_+") (pintype "passive"))
      (node (ref "C5") (pin "1") (pinfunction "1_1") (pintype "passive"))
      (node (ref "C9") (pin "1") (pinfunction "1_1") (pintype "passive"))
      (node (ref "ED1") (pin "1") (pinfunction "1_1") (pintype "passive"))
      (node (ref "ED2") (pin "1") (pinfunction "1_1") (pintype "passive"))
      (node (ref "ICSP") (pin "2") (pinfunction "2_2") (pintype "passive"))
      (node (ref "R15") (pin "1") (pinfunction "1_1") (pintype "passive"))
      (node (ref "R21") (pin "1") (pinfunction "1_1") (pintype "passive"))
      (node (ref "R3") (pin "1") (pinfunction "1_1") (pintype "passive"))
      (node (ref "R34") (pin "1") (pinfunction "1_1") (pintype "passive"))
      (node (ref "R35") (pin "1") (pinfunction "1_1") (pintype "passive"))
      (node (ref "R36") (pin "1") (pinfunction "1_1") (pintype "passive"))
      (node (ref "R40") (pin "1") (pinfunction "1_1") (pintype "passive"))
      (node (ref "R9") (pin "1") (pinfunction "1_1") (pintype "passive"))
      (node (ref "U1") (pin "21") (pinfunction "VCC_21") (pintype "bidirectional"))
      (node (ref "U1") (pin "3") (pinfunction "UVCC_3") (pintype "bidirectional"))
      (node (ref "U1") (pin "52") (pinfunction "VCC2_52") (pintype "bidirectional"))
      (node (ref "U1") (pin "62") (pinfunction "AREF_62") (pintype "bidirectional"))
      (node (ref "U1") (pin "64") (pinfunction "AVCC_64") (pintype "bidirectional"))
      (node (ref "U2") (pin "1") (pinfunction "RST_1") (pintype "bidirectional"))
      (node (ref "U2") (pin "11") (pinfunction "VCC_11") (pintype "bidirectional"))
      (node (ref "U2") (pin "4") (pinfunction "PS_4") (pintype "bidirectional"))
      (node (ref "U3") (pin "1") (pinfunction "RST_1") (pintype "bidirectional"))
      (node (ref "U3") (pin "11") (pinfunction "VCC_11") (pintype "bidirectional"))
      (node (ref "U3") (pin "4") (pinfunction "PS_4") (pintype "bidirectional"))
      (node (ref "U4") (pin "1") (pinfunction "RST_1") (pintype "bidirectional"))
      (node (ref "U4") (pin "11") (pinfunction "VCC_11") (pintype "bidirectional"))
      (node (ref "U4") (pin "4") (pinfunction "PS_4") (pintype "bidirectional"))
      (node (ref "U5") (pin "1") (pinfunction "RST_1") (pintype "bidirectional"))
      (node (ref "U5") (pin "11") (pinfunction "VCC_11") (pintype "bidirectional"))
      (node (ref "U5") (pin "4") (pinfunction "PS_4") (pintype "bidirectional"))
      (node (ref "U6") (pin "1") (pinfunction "OUT_1") (pintype "passive"))
      (node (ref "XD1") (pin "1") (pinfunction "1_1") (pintype "passive"))
      (node (ref "XD2") (pin "1") (pinfunction "1_1") (pintype "passive"))
      (node (ref "YD1") (pin "1") (pinfunction "1_1") (pintype "passive"))
      (node (ref "YD2") (pin "1") (pinfunction "1_1") (pintype "passive"))
      (node (ref "ZD1") (pin "1") (pinfunction "1_1") (pintype "passive"))
      (node (ref "ZD2") (pin "1") (pinfunction "1_1") (pintype "passive"))
    )
    (net (code "121") (name "unconnected-(U2-MONI-Pad5)") (class "Default")
      (node (ref "U2") (pin "5") (pinfunction "MONI_5") (pintype "bidirectional"))
    )
    (net (code "122") (name "unconnected-(U3-MONI-Pad5)") (class "Default")
      (node (ref "U3") (pin "5") (pinfunction "MONI_5") (pintype "bidirectional"))
    )
    (net (code "123") (name "unconnected-(U4-MONI-Pad5)") (class "Default")
      (node (ref "U4") (pin "5") (pinfunction "MONI_5") (pintype "bidirectional"))
    )
    (net (code "124") (name "unconnected-(U5-MONI-Pad5)") (class "Default")
      (node (ref "U5") (pin "5") (pinfunction "MONI_5") (pintype "bidirectional"))
    )
    (net (code "125") (name "unconnected-(X5-Pad4)") (class "Default")
      (node (ref "X5") (pin "4") (pinfunction "4_4") (pintype "input"))
    )
  )
)
